# 2DD-20-mk-1_0_0.net
KiCad netlist of a schematic drawn in EAGLE
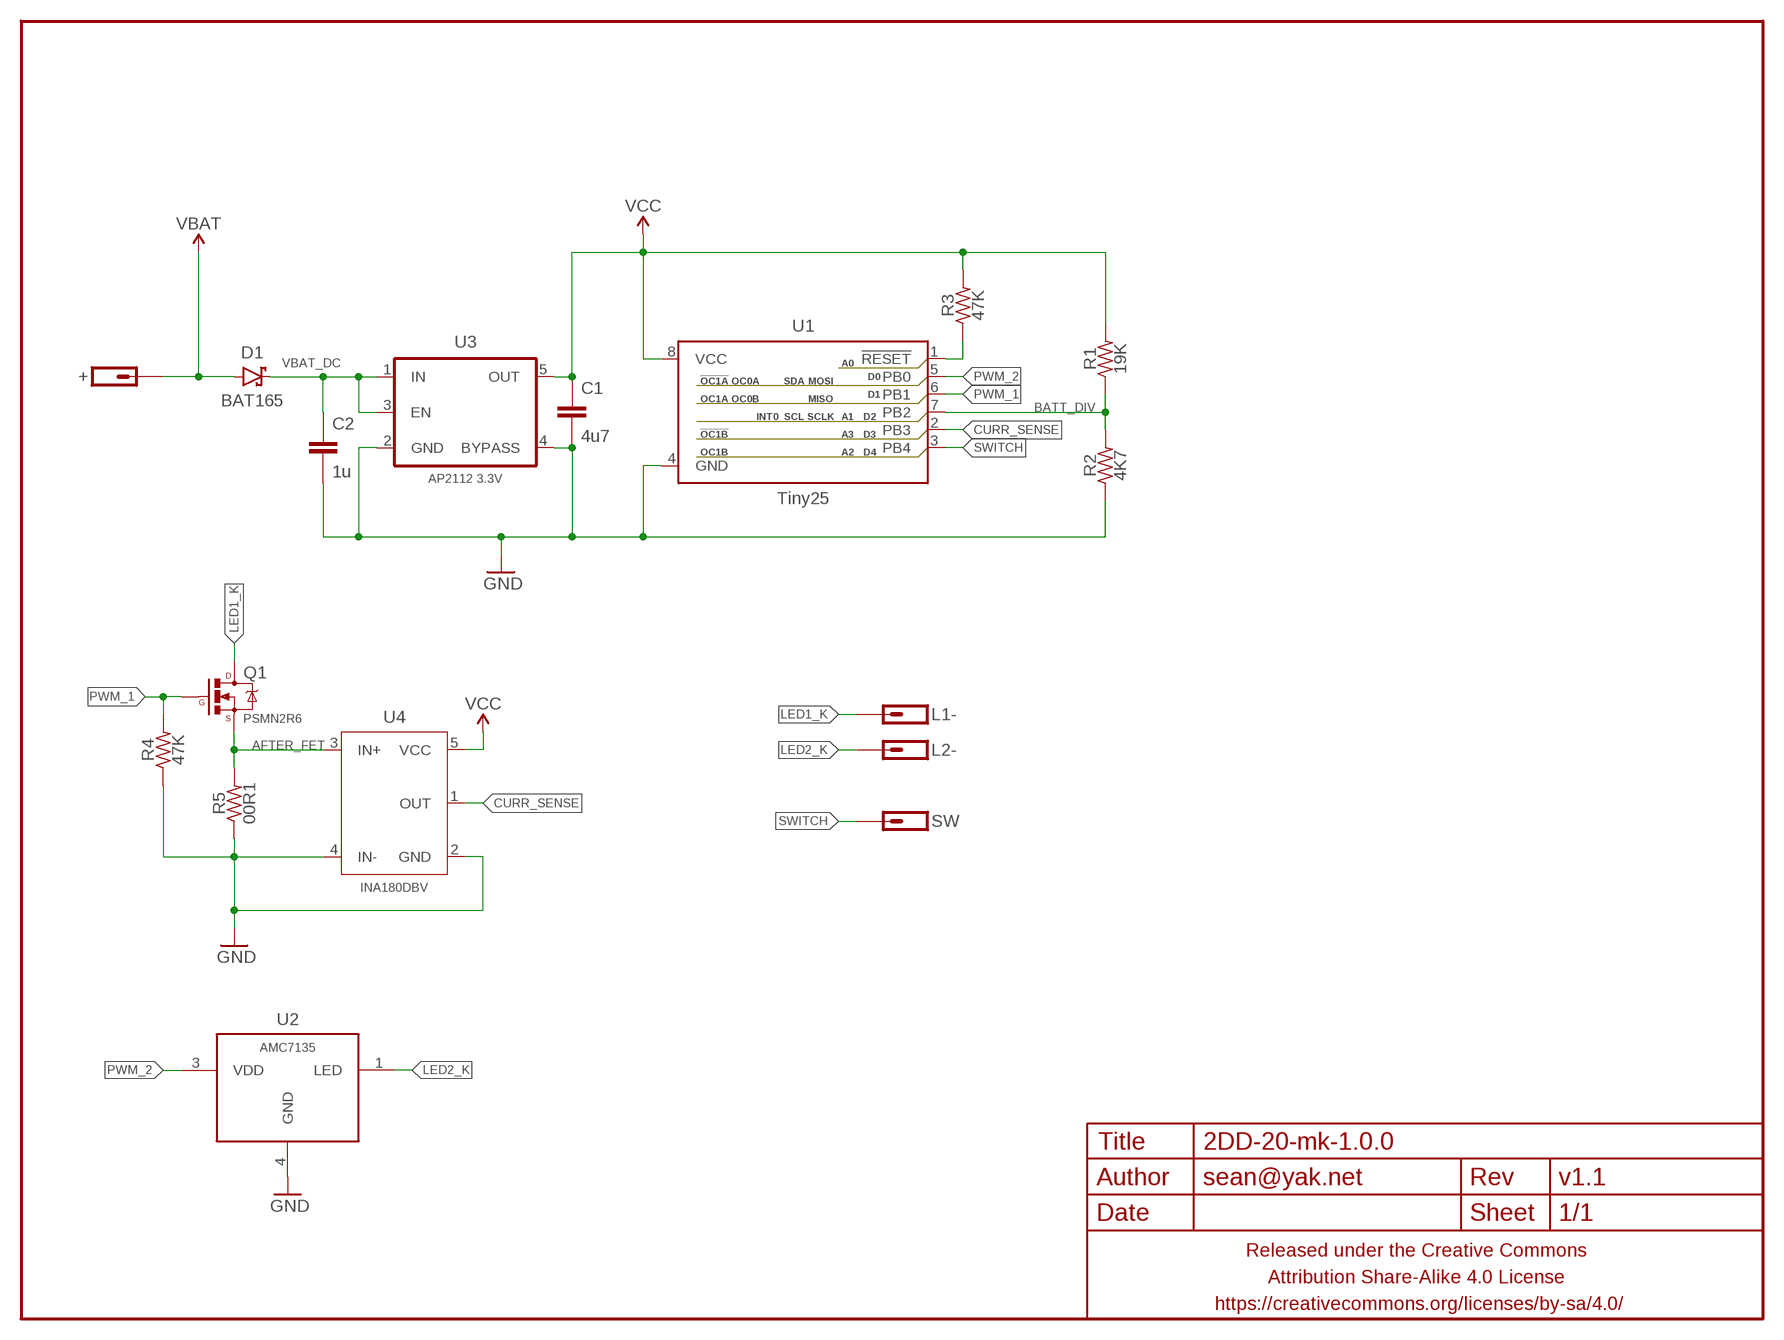
[diagram p0: schematic, sheet 1]

(export (version "E")
  (design (tool "Eeschema 10.0.6"))
  (components
    (comp (ref "+")
      (value "M01PTH-1MM-CIR-NS")
      (footprint "eagle-import:1X01-1MM-CIR-NS")
      (libsource (lib "eagle-import") (part "M01PTH-1MM-CIR-NS"))
    )
    (comp (ref "C1")
      (value "4u7")
      (footprint "eagle-import:C0603-TIGHTER")
      (libsource (lib "eagle-import") (part "CAPACITOR-CERAMICC0603-TIGHTER"))
    )
    (comp (ref "C2")
      (value "1u")
      (footprint "eagle-import:C0402")
      (libsource (lib "eagle-import") (part "CAPACITOR-CERAMICC0402"))
    )
    (comp (ref "D1")
      (value "BAT165")
      (footprint "eagle-import:SOD323-SCHOTTKY")
      (libsource (lib "eagle-import") (part "DIODE-SCHOTTKYSOD323"))
    )
    (comp (ref "FRAME1")
      (value "FRAME-LETTERNO_PACKAGE")
      (footprint "eagle-import:DUMMY")
      (fields (field (name "DESIGNER") "sean@yak.net") (field (name "VERSION") "v1.1"))
      (libsource (lib "eagle-import") (part "FRAME-LETTERNO_PACKAGE"))
    )
    (comp (ref "L1-")
      (value "M011X01-0.9MM-CIR")
      (footprint "eagle-import:1X01-0.9MM-CIR")
      (libsource (lib "eagle-import") (part "M011X01-0.9MM-CIR"))
    )
    (comp (ref "L2-")
      (value "M01PTH-0.8MM-CIR")
      (footprint "eagle-import:1X01-0.8MM-CIR")
      (libsource (lib "eagle-import") (part "M01PTH-0.8MM-CIR"))
    )
    (comp (ref "Q1")
      (value "PSMN2R6")
      (footprint "eagle-import:POWERPACK-SO-8")
      (libsource (lib "eagle-import") (part "MOSFET-NCHANNELSIR800DP"))
    )
    (comp (ref "R1")
      (value "19K")
      (footprint "eagle-import:R0402")
      (libsource (lib "eagle-import") (part "RESISTORR0402"))
    )
    (comp (ref "R2")
      (value "4K7")
      (footprint "eagle-import:R0402")
      (libsource (lib "eagle-import") (part "RESISTORR0402"))
    )
    (comp (ref "R3")
      (value "47K")
      (footprint "eagle-import:R0402")
      (libsource (lib "eagle-import") (part "RESISTORR0402"))
    )
    (comp (ref "R4")
      (value "47K")
      (footprint "eagle-import:R0402")
      (libsource (lib "eagle-import") (part "RESISTORR0402"))
    )
    (comp (ref "R5")
      (value "00R1")
      (footprint "eagle-import:R1206")
      (libsource (lib "eagle-import") (part "RESISTORR1206"))
    )
    (comp (ref "SW")
      (value "M01SMD-0.8MM-DIA-NS")
      (footprint "eagle-import:1X01-SMD-0.8MM-DIA-NS")
      (libsource (lib "eagle-import") (part "M01SMD-0.8MM-DIA-NS"))
    )
    (comp (ref "U1")
      (value "Tiny25")
      (footprint "eagle-import:SO08-NARROWER")
      (libsource (lib "eagle-import") (part "ATTINY13SOIC-NARROWPADS"))
    )
    (comp (ref "U2")
      (value "AMC7135")
      (footprint "eagle-import:SOT89-NOTHERM-ROUNDED-LESS")
      (libsource (lib "eagle-import") (part "AMC7135SOT-89-NOTHERM-ROUNDED-LESS"))
    )
    (comp (ref "U3")
      (value "AP2112 3.3V")
      (footprint "eagle-import:SOT23-5")
      (libsource (lib "eagle-import") (part "V_REG_SOT-23-5AP2112"))
    )
    (comp (ref "U4")
      (value "INA180DBV")
      (footprint "eagle-import:SOT23-5")
      (libsource (lib "eagle-import") (part "INA180DBV"))
    )
  )
  (nets
    (net (code "1") (name "/AFTER_FET") (class "Default")
      (node (ref "Q1") (pin "1") (pinfunction "S_1") (pintype "passive"))
      (node (ref "Q1") (pin "2") (pinfunction "S_2") (pintype "passive"))
      (node (ref "Q1") (pin "3") (pinfunction "S_3") (pintype "passive"))
      (node (ref "R5") (pin "2") (pinfunction "2_2") (pintype "passive"))
      (node (ref "U4") (pin "3") (pinfunction "IN+_3") (pintype "bidirectional"))
    )
    (net (code "2") (name "/BATT_DIV") (class "Default")
      (node (ref "R1") (pin "1") (pinfunction "1_1") (pintype "passive"))
      (node (ref "R2") (pin "2") (pinfunction "2_2") (pintype "passive"))
      (node (ref "U1") (pin "7") (pinfunction "PB2_7") (pintype "bidirectional"))
    )
    (net (code "3") (name "/VBAT_DC") (class "Default")
      (node (ref "C2") (pin "1") (pinfunction "1_1") (pintype "passive"))
      (node (ref "D1") (pin "C") (pinfunction "C_C") (pintype "passive"))
      (node (ref "U3") (pin "1") (pinfunction "IN_1") (pintype "input"))
      (node (ref "U3") (pin "3") (pinfunction "EN_3") (pintype "input"))
    )
    (net (code "4") (name "CURR_SENSE") (class "Default")
      (node (ref "U1") (pin "2") (pinfunction "PB3_2") (pintype "bidirectional"))
      (node (ref "U4") (pin "1") (pinfunction "OUT_1") (pintype "bidirectional"))
    )
    (net (code "5") (name "GND") (class "Default")
      (node (ref "C1") (pin "2") (pinfunction "2_2") (pintype "passive"))
      (node (ref "C2") (pin "2") (pinfunction "2_2") (pintype "passive"))
      (node (ref "R2") (pin "1") (pinfunction "1_1") (pintype "passive"))
      (node (ref "R4") (pin "1") (pinfunction "1_1") (pintype "passive"))
      (node (ref "R5") (pin "1") (pinfunction "1_1") (pintype "passive"))
      (node (ref "U1") (pin "4") (pinfunction "GND_4") (pintype "bidirectional"))
      (node (ref "U2") (pin "4") (pinfunction "GND_4") (pintype "bidirectional"))
      (node (ref "U3") (pin "2") (pinfunction "GND_2") (pintype "input"))
      (node (ref "U3") (pin "4") (pinfunction "BYPASS_4") (pintype "input"))
      (node (ref "U4") (pin "2") (pinfunction "GND_2") (pintype "bidirectional"))
      (node (ref "U4") (pin "4") (pinfunction "IN-_4") (pintype "bidirectional"))
    )
    (net (code "6") (name "LED1_K") (class "Default")
      (node (ref "L1-") (pin "P$1") (pinfunction "1_P$1") (pintype "passive"))
      (node (ref "Q1") (pin "5678") (pinfunction "D_5678") (pintype "passive"))
    )
    (net (code "7") (name "LED2_K") (class "Default")
      (node (ref "L2-") (pin "1") (pinfunction "1_1") (pintype "passive"))
      (node (ref "U2") (pin "1") (pinfunction "LED_1") (pintype "bidirectional"))
    )
    (net (code "8") (name "Net-(U1-~{RESET})") (class "Default")
      (node (ref "R3") (pin "1") (pinfunction "1_1") (pintype "passive"))
      (node (ref "U1") (pin "1") (pinfunction "~{RESET}_1") (pintype "bidirectional"))
    )
    (net (code "9") (name "PWM_1") (class "Default")
      (node (ref "Q1") (pin "4") (pinfunction "G_4") (pintype "passive"))
      (node (ref "R4") (pin "2") (pinfunction "2_2") (pintype "passive"))
      (node (ref "U1") (pin "6") (pinfunction "PB1_6") (pintype "bidirectional"))
    )
    (net (code "10") (name "PWM_2") (class "Default")
      (node (ref "U1") (pin "5") (pinfunction "PB0_5") (pintype "bidirectional"))
      (node (ref "U2") (pin "3") (pinfunction "VDD_3") (pintype "bidirectional"))
    )
    (net (code "11") (name "SWITCH") (class "Default")
      (node (ref "SW") (pin "P$1") (pinfunction "1_P$1") (pintype "passive"))
      (node (ref "U1") (pin "3") (pinfunction "PB4_3") (pintype "bidirectional"))
    )
    (net (code "12") (name "VBAT") (class "Default")
      (node (ref "+") (pin "1") (pinfunction "1_1") (pintype "passive"))
      (node (ref "D1") (pin "A") (pinfunction "A_A") (pintype "passive"))
    )
    (net (code "13") (name "VCC") (class "Default")
      (node (ref "C1") (pin "1") (pinfunction "1_1") (pintype "passive"))
      (node (ref "R1") (pin "2") (pinfunction "2_2") (pintype "passive"))
      (node (ref "R3") (pin "2") (pinfunction "2_2") (pintype "passive"))
      (node (ref "U1") (pin "8") (pinfunction "VCC_8") (pintype "bidirectional"))
      (node (ref "U3") (pin "5") (pinfunction "OUT_5") (pintype "passive"))
      (node (ref "U4") (pin "5") (pinfunction "VCC_5") (pintype "bidirectional"))
    )
  )
)
